# connector_pump.net
KiCad netlist of a schematic drawn in Altium Designer
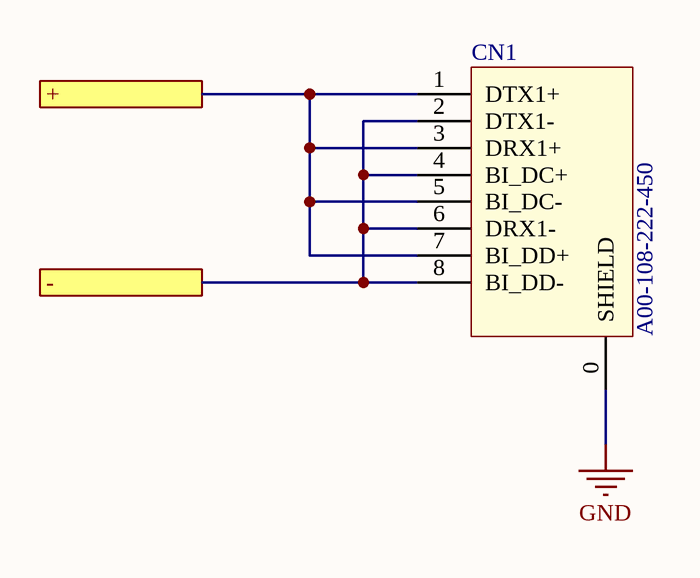
[diagram p0: connector_pump.SchDoc]

(export (version "E")
  (design (tool "Eeschema 10.0.6"))
  (components
    (comp (ref "CN1")
      (value "CONN_RJ45_TOP_A00-108-222-450")
      (footprint "RJ45 TOP ENTRY EDAC A00-108-222-450")
      (description "CONN, RJ-45, 1-PORT, 8-POS, VERT, 0.76um GOLD, TH")
      (fields (field (name "MFG") "EDAC Inc") (field (name "MFG P/N") "A00-108-222-450"))
      (libsource (lib "AltiumReleaseLibDB") (part "CONN_RJ45_TOP_A00-108-222-450"))
    )
  )
  (nets
    (net (code "1") (name "/+") (class "Default")
      (node (ref "CN1") (pin "1") (pinfunction "DTX1+_1") (pintype "passive"))
      (node (ref "CN1") (pin "3") (pinfunction "DRX1+_3") (pintype "passive"))
      (node (ref "CN1") (pin "5") (pinfunction "BI_DC-_5") (pintype "passive"))
      (node (ref "CN1") (pin "7") (pinfunction "BI_DD+_7") (pintype "passive"))
    )
    (net (code "2") (name "/-") (class "Default")
      (node (ref "CN1") (pin "2") (pinfunction "DTX1-_2") (pintype "passive"))
      (node (ref "CN1") (pin "4") (pinfunction "BI_DC+_4") (pintype "passive"))
      (node (ref "CN1") (pin "6") (pinfunction "DRX1-_6") (pintype "passive"))
      (node (ref "CN1") (pin "8") (pinfunction "BI_DD-_8") (pintype "passive"))
    )
    (net (code "3") (name "GND") (class "Default")
      (node (ref "CN1") (pin "0") (pinfunction "SHIELD_0") (pintype "passive"))
    )
  )
)
